# 795494688IHM08M1-DG_V4.net
KiCad netlist of a schematic drawn in Altium Designer
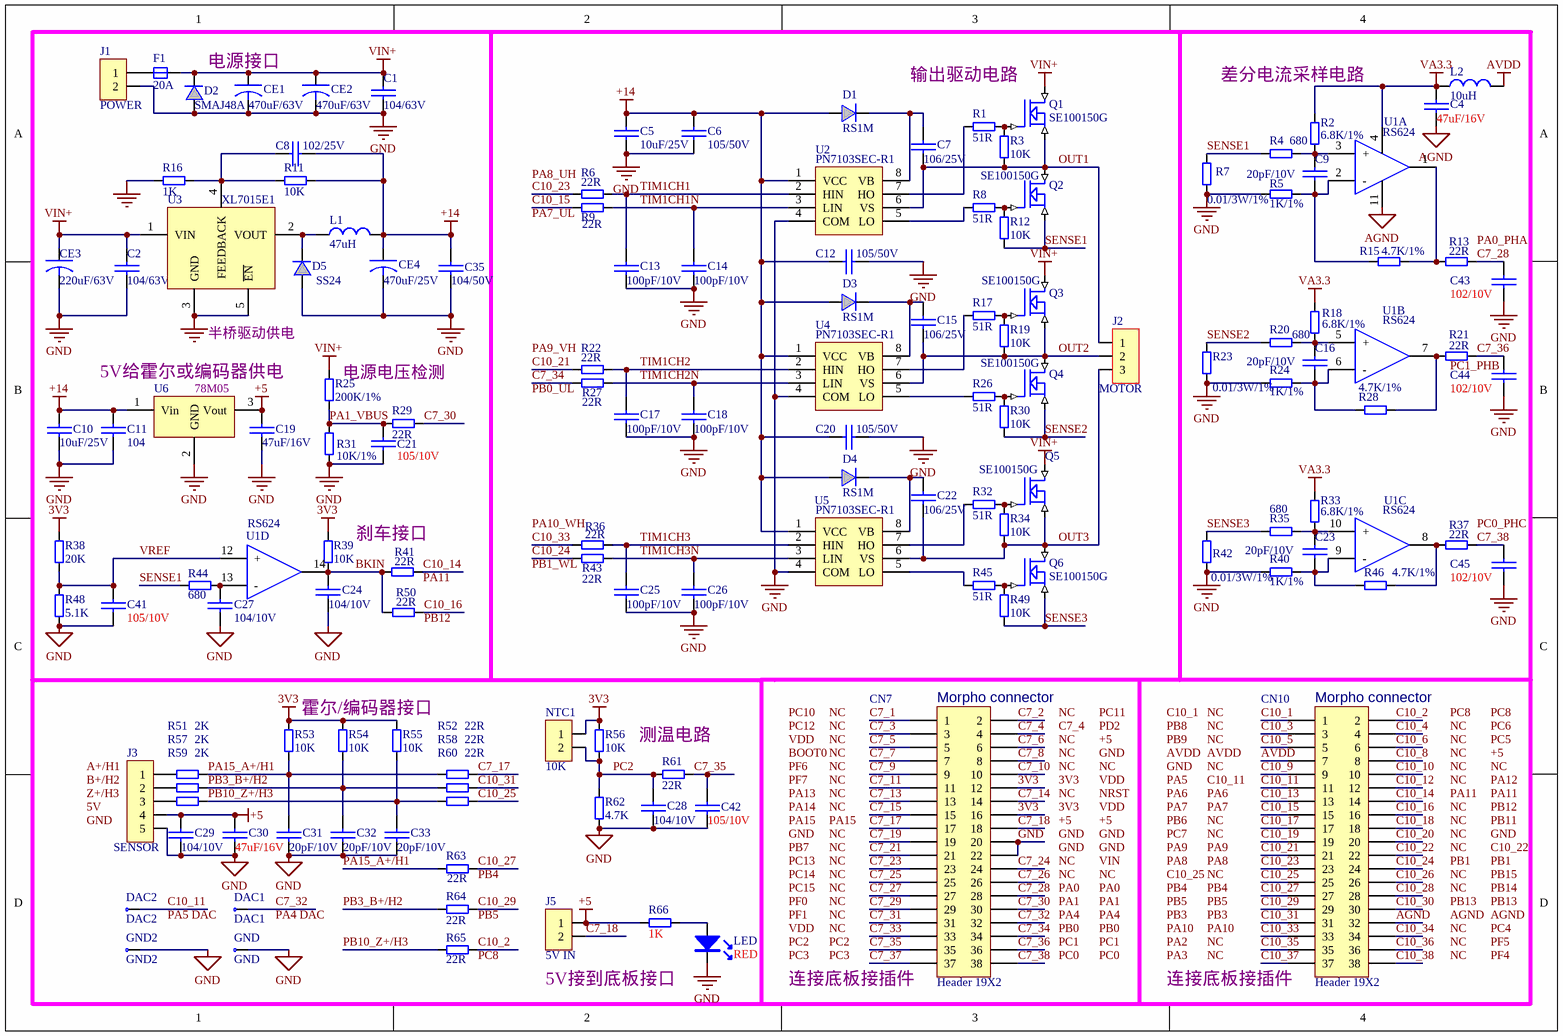
[diagram p0: 795494688IHM08M1-DG_V4.SchDoc]

(export (version "E")
  (design (tool "Eeschema 10.0.6"))
  (components
    (comp (ref "C1")
      (value "104/63V")
      (footprint "0805C")
      (description "C")
      (libsource (lib "zh") (part "C"))
    )
    (comp (ref "C2")
      (value "104/63V")
      (footprint "0805C")
      (description "C")
      (libsource (lib "zh") (part "C"))
    )
    (comp (ref "C4")
      (value "47uF/16V")
      (footprint "0805C")
      (description "C")
      (libsource (lib "zh") (part "C"))
    )
    (comp (ref "C5")
      (value "10uF/25V")
      (footprint "1206C")
      (description "Capacitor")
      (libsource (lib "*") (part "C"))
    )
    (comp (ref "C6")
      (value "105/50V")
      (footprint "0805C")
      (description "C")
      (libsource (lib "zh1") (part "C"))
    )
    (comp (ref "C7")
      (value "106/25V")
      (footprint "1206C")
      (description "C")
      (libsource (lib "zh1") (part "C"))
    )
    (comp (ref "C8")
      (value "102/25V")
      (footprint "0805C")
      (description "Capacitor")
      (libsource (lib "*") (part "C"))
    )
    (comp (ref "C9")
      (value "20pF/10V")
      (footprint "0603C")
      (description "C")
      (libsource (lib "zh") (part "C"))
    )
    (comp (ref "C10")
      (value "10uF/25V")
      (footprint "1206C")
      (description "Capacitor")
      (libsource (lib "*") (part "C"))
    )
    (comp (ref "C11")
      (value "104")
      (footprint "0805C")
      (description "Capacitor")
      (libsource (lib "*") (part "C"))
    )
    (comp (ref "C12")
      (value "105/50V")
      (footprint "0805C")
      (description "C")
      (libsource (lib "zh1") (part "C"))
    )
    (comp (ref "C13")
      (value "100pF/10V")
      (footprint "0603C")
      (description "C")
      (libsource (lib "zh") (part "C"))
    )
    (comp (ref "C14")
      (value "100pF/10V")
      (footprint "0603C")
      (description "C")
      (libsource (lib "zh") (part "C"))
    )
    (comp (ref "C15")
      (value "106/25V")
      (footprint "1206C")
      (description "C")
      (libsource (lib "zh1") (part "C"))
    )
    (comp (ref "C16")
      (value "20pF/10V")
      (footprint "0603C")
      (description "C")
      (libsource (lib "zh") (part "C"))
    )
    (comp (ref "C17")
      (value "100pF/10V")
      (footprint "0603C")
      (description "C")
      (libsource (lib "zh") (part "C"))
    )
    (comp (ref "C18")
      (value "100pF/10V")
      (footprint "0603C")
      (description "C")
      (libsource (lib "zh") (part "C"))
    )
    (comp (ref "C19")
      (value "47uF/16V")
      (footprint "1206C")
      (description "Capacitor")
      (libsource (lib "*") (part "C"))
    )
    (comp (ref "C20")
      (value "105/50V")
      (footprint "0805C")
      (description "C")
      (libsource (lib "zh1") (part "C"))
    )
    (comp (ref "C21")
      (value "105/10V")
      (footprint "0603C")
      (description "C")
      (libsource (lib "zh") (part "C"))
    )
    (comp (ref "C22")
      (value "106/25V")
      (footprint "1206C")
      (description "C")
      (libsource (lib "zh1") (part "C"))
    )
    (comp (ref "C23")
      (value "20pF/10V")
      (footprint "0603C")
      (description "C")
      (libsource (lib "zh") (part "C"))
    )
    (comp (ref "C24")
      (value "104/10V")
      (footprint "0603C")
      (description "C")
      (libsource (lib "zh") (part "C"))
    )
    (comp (ref "C25")
      (value "100pF/10V")
      (footprint "0603C")
      (description "C")
      (libsource (lib "zh") (part "C"))
    )
    (comp (ref "C26")
      (value "100pF/10V")
      (footprint "0603C")
      (description "C")
      (libsource (lib "zh") (part "C"))
    )
    (comp (ref "C27")
      (value "104/10V")
      (footprint "0603C")
      (description "C")
      (libsource (lib "zh") (part "C"))
    )
    (comp (ref "C28")
      (value "104/10V")
      (footprint "0603C")
      (description "C")
      (libsource (lib "zh") (part "C"))
    )
    (comp (ref "C29")
      (value "104/10V")
      (footprint "0603C")
      (description "C")
      (libsource (lib "zh") (part "C"))
    )
    (comp (ref "C30")
      (value "47uF/16V")
      (footprint "0805C")
      (description "C")
      (libsource (lib "zh") (part "C"))
    )
    (comp (ref "C31")
      (value "20pF/10V")
      (footprint "0603C")
      (description "C")
      (libsource (lib "zh") (part "C"))
    )
    (comp (ref "C32")
      (value "20pF/10V")
      (footprint "0603C")
      (description "C")
      (libsource (lib "zh") (part "C"))
    )
    (comp (ref "C33")
      (value "20pF/10V")
      (footprint "0603C")
      (description "C")
      (libsource (lib "zh") (part "C"))
    )
    (comp (ref "C35")
      (value "104/50V")
      (footprint "0805C")
      (description "C")
      (libsource (lib "zh") (part "C"))
    )
    (comp (ref "C41")
      (value "105/10V")
      (footprint "0603C")
      (description "C")
      (libsource (lib "zh") (part "C"))
    )
    (comp (ref "C42")
      (value "105/10V")
      (footprint "0603C")
      (description "C")
      (libsource (lib "zh") (part "C"))
    )
    (comp (ref "C43")
      (value "102/10V")
      (footprint "0603C")
      (description "C")
      (libsource (lib "zh") (part "C"))
    )
    (comp (ref "C44")
      (value "102/10V")
      (footprint "0603C")
      (description "C")
      (libsource (lib "zh") (part "C"))
    )
    (comp (ref "C45")
      (value "102/10V")
      (footprint "0603C")
      (description "C")
      (libsource (lib "zh") (part "C"))
    )
    (comp (ref "CE1")
      (value "470uF/63V")
      (footprint "E5-12.5")
      (description "10uF/25V")
      (libsource (lib "zh") (part "CE"))
    )
    (comp (ref "CE2")
      (value "470uF/63V")
      (footprint "E5-12.5")
      (description "10uF/25V")
      (libsource (lib "zh") (part "CE"))
    )
    (comp (ref "CE3")
      (value "220uF/63V")
      (footprint "E5-10")
      (description "10uF/25V")
      (libsource (lib "zh") (part "CE"))
    )
    (comp (ref "CE4")
      (value "470uF/25V")
      (footprint "E3.5-8.2")
      (description "10uF/25V")
      (libsource (lib "zh") (part "CE"))
    )
    (comp (ref "CN7")
      (value "Header 19X2")
      (footprint "2*19P")
      (description "Header, 19-Pin, Dual row")
      (fields (field (name "PUBLISHER") "Altium Limited"))
      (libsource (lib "Nucleo_64_1") (part "Header 19X2"))
    )
    (comp (ref "CN10")
      (value "Header 19X2")
      (footprint "2*19P")
      (description "Header, 19-Pin, Dual row")
      (fields (field (name "PUBLISHER") "Altium Limited"))
      (libsource (lib "Nucleo_64_1") (part "Header 19X2"))
    )
    (comp (ref "D1") (value "RS1M") (footprint "TP4007") (description "D") (libsource (lib "zh1") (part "D")))
    (comp (ref "D2")
      (value "SMAJ48A")
      (footprint "TPss24")
      (description "D")
      (libsource (lib "zh") (part "D"))
    )
    (comp (ref "D3") (value "RS1M") (footprint "TP4007") (description "D") (libsource (lib "zh1") (part "D")))
    (comp (ref "D4") (value "RS1M") (footprint "TP4007") (description "D") (libsource (lib "zh1") (part "D")))
    (comp (ref "D5") (value "SS24") (footprint "TPss24") (description "D") (libsource (lib "zh") (part "D")))
    (comp (ref "DAC1") (value "DAC1") (footprint "TP-1.5") (libsource (lib "zh") (part "TP")))
    (comp (ref "DAC2") (value "DAC2") (footprint "TP-1.5") (libsource (lib "zh") (part "TP")))
    (comp (ref "F1")
      (value "20A")
      (footprint "F1808")
      (description "FUSE")
      (libsource (lib "zh") (part "FUSE"))
    )
    (comp (ref "GND") (value "GND") (footprint "TP-1.5") (libsource (lib "zh") (part "TP")))
    (comp (ref "GND2") (value "GND2") (footprint "TP-1.5") (libsource (lib "zh") (part "TP")))
    (comp (ref "J1")
      (value "POWER")
      (footprint "POW-5.08-2W")
      (description "J")
      (libsource (lib "zh") (part "CON2"))
    )
    (comp (ref "J2")
      (value "MOTOR")
      (footprint "POW-5.08-3W")
      (description "CN")
      (libsource (lib "zh") (part "CON3"))
    )
    (comp (ref "J3")
      (value "SENSOR")
      (footprint "SIP5")
      (description "CN")
      (libsource (lib "zh") (part "CON5"))
    )
    (comp (ref "J5")
      (value "5V IN")
      (footprint "SIP2")
      (description "J")
      (libsource (lib "zh") (part "CON2"))
    )
    (comp (ref "L1")
      (value "47uH")
      (footprint "L-TB-7*7")
      (description "10uH")
      (libsource (lib "zh1") (part "L"))
    )
    (comp (ref "L2") (value "10uH") (footprint "0603") (libsource (lib "zh1") (part "L")))
    (comp (ref "LED")
      (value "RED")
      (footprint "0603D")
      (description "LED")
      (libsource (lib "zh") (part "LED"))
    )
    (comp (ref "NTC1")
      (value "10K")
      (footprint "SIP2")
      (description "J")
      (libsource (lib "zh") (part "CON2"))
    )
    (comp (ref "Q1") (value "SE100150G") (footprint "TO-263S") (libsource (lib "zh1") (part "MOSFET N")))
    (comp (ref "Q2") (value "SE100150G") (footprint "TO-263S") (libsource (lib "zh1") (part "MOSFET N")))
    (comp (ref "Q3") (value "SE100150G") (footprint "TO-263S") (libsource (lib "zh1") (part "MOSFET N")))
    (comp (ref "Q4") (value "SE100150G") (footprint "TO-263S") (libsource (lib "zh1") (part "MOSFET N")))
    (comp (ref "Q5") (value "SE100150G") (footprint "TO-263S") (libsource (lib "zh1") (part "MOSFET N")))
    (comp (ref "Q6") (value "SE100150G") (footprint "TO-263S") (libsource (lib "zh1") (part "MOSFET N")))
    (comp (ref "R1") (value "51R") (footprint "0805") (description "10K") (libsource (lib "zh1") (part "R")))
    (comp (ref "R2")
      (value "6.8K/1%")
      (footprint "0603")
      (description "10K")
      (libsource (lib "zh") (part "R"))
    )
    (comp (ref "R3") (value "10K") (footprint "0603") (libsource (lib "zh") (part "R")))
    (comp (ref "R4") (value "680") (footprint "0603") (description "10K") (libsource (lib "zh") (part "R")))
    (comp (ref "R5") (value "1K/1%") (footprint "0603") (description "10K") (libsource (lib "zh") (part "R")))
    (comp (ref "R6") (value "22R") (footprint "0603") (description "10K") (libsource (lib "zh") (part "R")))
    (comp (ref "R7")
      (value "0.01/3W/1%")
      (footprint "2512")
      (description "10K")
      (libsource (lib "zh") (part "R"))
    )
    (comp (ref "R8") (value "51R") (footprint "0805") (description "10K") (libsource (lib "zh1") (part "R")))
    (comp (ref "R9") (value "22R") (footprint "0603") (description "10K") (libsource (lib "zh") (part "R")))
    (comp (ref "R11") (value "10K") (footprint "0603") (libsource (lib "zh") (part "R")))
    (comp (ref "R12") (value "10K") (footprint "0603") (libsource (lib "zh") (part "R")))
    (comp (ref "R13") (value "22R") (footprint "0603") (description "10K") (libsource (lib "zh") (part "R")))
    (comp (ref "R15")
      (value "4.7K/1%")
      (footprint "0603")
      (description "10K")
      (libsource (lib "zh") (part "R"))
    )
    (comp (ref "R16") (value "1K") (footprint "0603") (description "10K") (libsource (lib "zh") (part "R")))
    (comp (ref "R17") (value "51R") (footprint "0805") (description "10K") (libsource (lib "zh1") (part "R")))
    (comp (ref "R18")
      (value "6.8K/1%")
      (footprint "0603")
      (description "10K")
      (libsource (lib "zh") (part "R"))
    )
    (comp (ref "R19") (value "10K") (footprint "0603") (libsource (lib "zh") (part "R")))
    (comp (ref "R20") (value "680") (footprint "0603") (description "10K") (libsource (lib "zh") (part "R")))
    (comp (ref "R21") (value "22R") (footprint "0603") (description "10K") (libsource (lib "zh") (part "R")))
    (comp (ref "R22") (value "22R") (footprint "0603") (description "10K") (libsource (lib "zh") (part "R")))
    (comp (ref "R23")
      (value "0.01/3W/1%")
      (footprint "2512")
      (description "10K")
      (libsource (lib "zh") (part "R"))
    )
    (comp (ref "R24")
      (value "1K/1%")
      (footprint "0603")
      (description "10K")
      (libsource (lib "zh") (part "R"))
    )
    (comp (ref "R25")
      (value "200K/1%")
      (footprint "0603")
      (description "10K")
      (libsource (lib "zh") (part "R"))
    )
    (comp (ref "R26") (value "51R") (footprint "0805") (description "10K") (libsource (lib "zh1") (part "R")))
    (comp (ref "R27") (value "22R") (footprint "0603") (description "10K") (libsource (lib "zh") (part "R")))
    (comp (ref "R28")
      (value "4.7K/1%")
      (footprint "0603")
      (description "10K")
      (libsource (lib "zh") (part "R"))
    )
    (comp (ref "R29") (value "22R") (footprint "0603") (description "10K") (libsource (lib "zh") (part "R")))
    (comp (ref "R30") (value "10K") (footprint "0603") (libsource (lib "zh") (part "R")))
    (comp (ref "R31")
      (value "10K/1%")
      (footprint "0603")
      (description "10K")
      (libsource (lib "zh") (part "R"))
    )
    (comp (ref "R32") (value "51R") (footprint "0805") (description "10K") (libsource (lib "zh1") (part "R")))
    (comp (ref "R33")
      (value "6.8K/1%")
      (footprint "0603")
      (description "10K")
      (libsource (lib "zh") (part "R"))
    )
    (comp (ref "R34") (value "10K") (footprint "0603") (libsource (lib "zh") (part "R")))
    (comp (ref "R35") (value "680") (footprint "0603") (description "10K") (libsource (lib "zh") (part "R")))
    (comp (ref "R36") (value "22R") (footprint "0603") (description "10K") (libsource (lib "zh") (part "R")))
    (comp (ref "R37") (value "22R") (footprint "0603") (description "10K") (libsource (lib "zh") (part "R")))
    (comp (ref "R38") (value "20K") (footprint "0603") (description "10K") (libsource (lib "zh") (part "R")))
    (comp (ref "R39") (value "10K") (footprint "0603") (libsource (lib "zh") (part "R")))
    (comp (ref "R40")
      (value "1K/1%")
      (footprint "0603")
      (description "10K")
      (libsource (lib "zh") (part "R"))
    )
    (comp (ref "R41") (value "22R") (footprint "0603") (description "10K") (libsource (lib "zh") (part "R")))
    (comp (ref "R42")
      (value "0.01/3W/1%")
      (footprint "2512")
      (description "10K")
      (libsource (lib "zh") (part "R"))
    )
    (comp (ref "R43") (value "22R") (footprint "0603") (description "10K") (libsource (lib "zh") (part "R")))
    (comp (ref "R44") (value "680") (footprint "0603") (description "10K") (libsource (lib "zh") (part "R")))
    (comp (ref "R45") (value "51R") (footprint "0805") (description "10K") (libsource (lib "zh1") (part "R")))
    (comp (ref "R46")
      (value "4.7K/1%")
      (footprint "0603")
      (description "10K")
      (libsource (lib "zh") (part "R"))
    )
    (comp (ref "R48") (value "5.1K") (footprint "0603") (description "10K") (libsource (lib "zh") (part "R")))
    (comp (ref "R49") (value "10K") (footprint "0603") (libsource (lib "zh") (part "R")))
    (comp (ref "R50") (value "22R") (footprint "0603") (description "10K") (libsource (lib "zh") (part "R")))
    (comp (ref "R51") (value "2K") (footprint "0603") (description "10K") (libsource (lib "zh") (part "R")))
    (comp (ref "R52") (value "22R") (footprint "0603") (description "10K") (libsource (lib "zh") (part "R")))
    (comp (ref "R53") (value "10K") (footprint "0603") (libsource (lib "zh") (part "R")))
    (comp (ref "R54") (value "10K") (footprint "0603") (libsource (lib "zh") (part "R")))
    (comp (ref "R55") (value "10K") (footprint "0603") (libsource (lib "zh") (part "R")))
    (comp (ref "R56") (value "10K") (footprint "0805") (libsource (lib "zh") (part "R")))
    (comp (ref "R57") (value "2K") (footprint "0603") (description "10K") (libsource (lib "zh") (part "R")))
    (comp (ref "R58") (value "22R") (footprint "0603") (description "10K") (libsource (lib "zh") (part "R")))
    (comp (ref "R59") (value "2K") (footprint "0603") (description "10K") (libsource (lib "zh") (part "R")))
    (comp (ref "R60") (value "22R") (footprint "0603") (description "10K") (libsource (lib "zh") (part "R")))
    (comp (ref "R61") (value "22R") (footprint "0603") (description "10K") (libsource (lib "zh") (part "R")))
    (comp (ref "R62") (value "4.7K") (footprint "0603") (description "10K") (libsource (lib "zh") (part "R")))
    (comp (ref "R63") (value "22R") (footprint "0603") (description "10K") (libsource (lib "zh") (part "R")))
    (comp (ref "R64") (value "22R") (footprint "0603") (description "10K") (libsource (lib "zh") (part "R")))
    (comp (ref "R65") (value "22R") (footprint "0603") (description "10K") (libsource (lib "zh") (part "R")))
    (comp (ref "R66") (value "1K") (footprint "0603") (description "10K") (libsource (lib "zh") (part "R")))
    (comp (ref "U1") (value "RS624") (footprint "SO-14") (libsource (lib "LY-SCH") (part "LM324")))
    (comp (ref "U2") (value "PN7103SEC-R1") (footprint "SO-8") (libsource (lib "zh1") (part "IR2101S")))
    (comp (ref "U3")
      (value "XL7015E1")
      (footprint "TO-252-5L")
      (libsource (lib "LY-SCH") (part "XL1507-ADJ"))
    )
    (comp (ref "U4") (value "PN7103SEC-R1") (footprint "SO-8") (libsource (lib "zh1") (part "IR2101S")))
    (comp (ref "U5") (value "PN7103SEC-R1") (footprint "SO-8") (libsource (lib "zh1") (part "IR2101S")))
    (comp (ref "U6")
      (value "78M05")
      (footprint "TO-252AA")
      (description "IC")
      (libsource (lib "zh1") (part "7805S"))
    )
  )
  (nets
    (net (code "1") (name "+5") (class "Default")
      (node (ref "C19") (pin "2") (pintype "passive"))
      (node (ref "C29") (pin "1") (pintype "passive"))
      (node (ref "C30") (pin "1") (pintype "passive"))
      (node (ref "J3") (pin "4") (pinfunction "4_4") (pintype "passive"))
      (node (ref "J5") (pin "1") (pinfunction "1_1") (pintype "passive"))
      (node (ref "R66") (pin "2") (pinfunction "2_2") (pintype "passive"))
      (node (ref "U6") (pin "3") (pinfunction "Vout_3") (pintype "passive"))
    )
    (net (code "2") (name "+14") (class "Default")
      (node (ref "C10") (pin "2") (pintype "passive"))
      (node (ref "C11") (pin "2") (pintype "passive"))
      (node (ref "C12") (pin "1") (pintype "passive"))
      (node (ref "C20") (pin "1") (pintype "passive"))
      (node (ref "C35") (pin "1") (pintype "passive"))
      (node (ref "C5") (pin "2") (pintype "passive"))
      (node (ref "C6") (pin "1") (pintype "passive"))
      (node (ref "C8") (pin "1") (pintype "passive"))
      (node (ref "CE4") (pin "1") (pinfunction "1_1") (pintype "passive"))
      (node (ref "D1") (pin "A") (pinfunction "1_A") (pintype "passive"))
      (node (ref "D3") (pin "A") (pinfunction "1_A") (pintype "passive"))
      (node (ref "D4") (pin "A") (pinfunction "1_A") (pintype "passive"))
      (node (ref "L1") (pin "2") (pinfunction "2_2") (pintype "passive"))
      (node (ref "R11") (pin "2") (pinfunction "2_2") (pintype "passive"))
      (node (ref "U2") (pin "1") (pinfunction "VCC_1") (pintype "passive"))
      (node (ref "U4") (pin "1") (pinfunction "VCC_1") (pintype "passive"))
      (node (ref "U5") (pin "1") (pinfunction "VCC_1") (pintype "passive"))
      (node (ref "U6") (pin "1") (pinfunction "Vin_1") (pintype "passive"))
    )
    (net (code "6") (name "/BKIN") (class "Default")
      (node (ref "C24") (pin "1") (pintype "passive"))
      (node (ref "R39") (pin "1") (pinfunction "1_1") (pintype "passive"))
      (node (ref "R41") (pin "1") (pinfunction "1_1") (pintype "passive"))
      (node (ref "R50") (pin "1") (pinfunction "1_1") (pintype "passive"))
      (node (ref "U1") (pin "14") (pinfunction "O_14") (pintype "passive"))
    )
    (net (code "8") (name "/C7_1") (class "Default")
      (node (ref "CN7") (pin "1") (pinfunction "1_1") (pintype "passive"))
    )
    (net (code "9") (name "/C7_2") (class "Default")
      (node (ref "CN7") (pin "2") (pinfunction "2_2") (pintype "passive"))
    )
    (net (code "10") (name "/C7_3") (class "Default")
      (node (ref "CN7") (pin "3") (pinfunction "3_3") (pintype "passive"))
    )
    (net (code "11") (name "/C7_4") (class "Default")
      (node (ref "CN7") (pin "4") (pinfunction "4_4") (pintype "passive"))
    )
    (net (code "12") (name "/C7_5") (class "Default")
      (node (ref "CN7") (pin "5") (pinfunction "5_5") (pintype "passive"))
    )
    (net (code "13") (name "/C7_6") (class "Default")
      (node (ref "CN7") (pin "6") (pinfunction "6_6") (pintype "passive"))
    )
    (net (code "14") (name "/C7_7") (class "Default")
      (node (ref "CN7") (pin "7") (pinfunction "7_7") (pintype "passive"))
    )
    (net (code "15") (name "/C7_8") (class "Default")
      (node (ref "CN7") (pin "8") (pinfunction "8_8") (pintype "passive"))
    )
    (net (code "16") (name "/C7_9") (class "Default")
      (node (ref "CN7") (pin "9") (pinfunction "9_9") (pintype "passive"))
    )
    (net (code "17") (name "/C7_10") (class "Default")
      (node (ref "CN7") (pin "10") (pinfunction "10_10") (pintype "passive"))
    )
    (net (code "18") (name "/C7_11") (class "Default")
      (node (ref "CN7") (pin "11") (pinfunction "11_11") (pintype "passive"))
    )
    (net (code "19") (name "/C7_13") (class "Default")
      (node (ref "CN7") (pin "13") (pinfunction "13_13") (pintype "passive"))
    )
    (net (code "20") (name "/C7_14") (class "Default")
      (node (ref "CN7") (pin "14") (pinfunction "14_14") (pintype "passive"))
    )
    (net (code "21") (name "/C7_15") (class "Default")
      (node (ref "CN7") (pin "15") (pinfunction "15_15") (pintype "passive"))
    )
    (net (code "22") (name "/C7_17") (class "Default")
      (node (ref "CN7") (pin "17") (pinfunction "17_17") (pintype "passive"))
      (node (ref "R52") (pin "1") (pinfunction "1_1") (pintype "passive"))
    )
    (net (code "23") (name "/C7_18") (class "Default")
      (node (ref "CN7") (pin "18") (pinfunction "18_18") (pintype "passive"))
      (node (ref "J5") (pin "2") (pinfunction "2_2") (pintype "passive"))
    )
    (net (code "24") (name "/C7_19") (class "Default")
      (node (ref "CN7") (pin "19") (pinfunction "19_19") (pintype "passive"))
    )
    (net (code "25") (name "/C7_21") (class "Default")
      (node (ref "CN7") (pin "21") (pinfunction "21_21") (pintype "passive"))
    )
    (net (code "26") (name "/C7_23") (class "Default")
      (node (ref "CN7") (pin "23") (pinfunction "23_23") (pintype "passive"))
    )
    (net (code "27") (name "/C7_24") (class "Default")
      (node (ref "CN7") (pin "24") (pinfunction "24_24") (pintype "passive"))
    )
    (net (code "28") (name "/C7_25") (class "Default")
      (node (ref "CN7") (pin "25") (pinfunction "25_25") (pintype "passive"))
    )
    (net (code "29") (name "/C7_26") (class "Default")
      (node (ref "CN7") (pin "26") (pinfunction "26_26") (pintype "passive"))
    )
    (net (code "30") (name "/C7_27") (class "Default")
      (node (ref "CN7") (pin "27") (pinfunction "27_27") (pintype "passive"))
    )
    (net (code "31") (name "/C7_28") (class "Default")
      (node (ref "C43") (pin "1") (pintype "passive"))
      (node (ref "CN7") (pin "28") (pinfunction "28_28") (pintype "passive"))
      (node (ref "R13") (pin "2") (pinfunction "2_2") (pintype "passive"))
    )
    (net (code "32") (name "/C7_29") (class "Default")
      (node (ref "CN7") (pin "29") (pinfunction "29_29") (pintype "passive"))
    )
    (net (code "33") (name "/C7_30") (class "Default")
      (node (ref "CN7") (pin "30") (pinfunction "30_30") (pintype "passive"))
      (node (ref "R29") (pin "2") (pinfunction "2_2") (pintype "passive"))
    )
    (net (code "34") (name "/C7_31") (class "Default")
      (node (ref "CN7") (pin "31") (pinfunction "31_31") (pintype "passive"))
    )
    (net (code "35") (name "/C7_32") (class "Default")
      (node (ref "CN7") (pin "32") (pinfunction "32_32") (pintype "passive"))
      (node (ref "DAC1") (pin "1") (pinfunction "1_1") (pintype "passive"))
    )
    (net (code "36") (name "/C7_33") (class "Default")
      (node (ref "CN7") (pin "33") (pinfunction "33_33") (pintype "passive"))
    )
    (net (code "37") (name "/C7_34") (class "Default")
      (node (ref "CN7") (pin "34") (pinfunction "34_34") (pintype "passive"))
      (node (ref "R27") (pin "1") (pinfunction "1_1") (pintype "passive"))
    )
    (net (code "38") (name "/C7_35") (class "Default")
      (node (ref "C42") (pin "1") (pintype "passive"))
      (node (ref "CN7") (pin "35") (pinfunction "35_35") (pintype "passive"))
      (node (ref "R61") (pin "1") (pinfunction "1_1") (pintype "passive"))
    )
    (net (code "39") (name "/C7_36") (class "Default")
      (node (ref "C44") (pin "1") (pintype "passive"))
      (node (ref "CN7") (pin "36") (pinfunction "36_36") (pintype "passive"))
      (node (ref "R21") (pin "2") (pinfunction "2_2") (pintype "passive"))
    )
    (net (code "40") (name "/C7_37") (class "Default")
      (node (ref "CN7") (pin "37") (pinfunction "37_37") (pintype "passive"))
    )
    (net (code "41") (name "/C7_38") (class "Default")
      (node (ref "C45") (pin "1") (pintype "passive"))
      (node (ref "CN7") (pin "38") (pinfunction "38_38") (pintype "passive"))
      (node (ref "R37") (pin "2") (pinfunction "2_2") (pintype "passive"))
    )
    (net (code "42") (name "/C10_1") (class "Default")
      (node (ref "CN10") (pin "1") (pinfunction "1_1") (pintype "passive"))
    )
    (net (code "43") (name "/C10_2") (class "Default")
      (node (ref "CN10") (pin "2") (pinfunction "2_2") (pintype "passive"))
      (node (ref "R65") (pin "1") (pinfunction "1_1") (pintype "passive"))
    )
    (net (code "44") (name "/C10_3") (class "Default")
      (node (ref "CN10") (pin "3") (pinfunction "3_3") (pintype "passive"))
    )
    (net (code "45") (name "/C10_4") (class "Default")
      (node (ref "CN10") (pin "4") (pinfunction "4_4") (pintype "passive"))
    )
    (net (code "46") (name "/C10_5") (class "Default")
      (node (ref "CN10") (pin "5") (pinfunction "5_5") (pintype "passive"))
    )
    (net (code "47") (name "/C10_6") (class "Default")
      (node (ref "CN10") (pin "6") (pinfunction "6_6") (pintype "passive"))
    )
    (net (code "48") (name "/C10_8") (class "Default")
      (node (ref "CN10") (pin "8") (pinfunction "8_8") (pintype "passive"))
    )
    (net (code "49") (name "/C10_9") (class "Default")
      (node (ref "CN10") (pin "9") (pinfunction "9_9") (pintype "passive"))
    )
    (net (code "50") (name "/C10_10") (class "Default")
      (node (ref "CN10") (pin "10") (pinfunction "10_10") (pintype "passive"))
    )
    (net (code "51") (name "/C10_11") (class "Default")
      (node (ref "CN10") (pin "11") (pinfunction "11_11") (pintype "passive"))
      (node (ref "DAC2") (pin "1") (pinfunction "1_1") (pintype "passive"))
    )
    (net (code "52") (name "/C10_12") (class "Default")
      (node (ref "CN10") (pin "12") (pinfunction "12_12") (pintype "passive"))
    )
    (net (code "53") (name "/C10_13") (class "Default")
      (node (ref "CN10") (pin "13") (pinfunction "13_13") (pintype "passive"))
    )
    (net (code "54") (name "/C10_14") (class "Default")
      (node (ref "CN10") (pin "14") (pinfunction "14_14") (pintype "passive"))
      (node (ref "R41") (pin "2") (pinfunction "2_2") (pintype "passive"))
    )
    (net (code "55") (name "/C10_15") (class "Default")
      (node (ref "CN10") (pin "15") (pinfunction "15_15") (pintype "passive"))
      (node (ref "R9") (pin "1") (pinfunction "1_1") (pintype "passive"))
    )
    (net (code "56") (name "/C10_16") (class "Default")
      (node (ref "CN10") (pin "16") (pinfunction "16_16") (pintype "passive"))
      (node (ref "R50") (pin "2") (pinfunction "2_2") (pintype "passive"))
    )
    (net (code "57") (name "/C10_17") (class "Default")
      (node (ref "CN10") (pin "17") (pinfunction "17_17") (pintype "passive"))
    )
    (net (code "58") (name "/C10_18") (class "Default")
      (node (ref "CN10") (pin "18") (pinfunction "18_18") (pintype "passive"))
    )
    (net (code "59") (name "/C10_19") (class "Default")
      (node (ref "CN10") (pin "19") (pinfunction "19_19") (pintype "passive"))
    )
    (net (code "60") (name "/C10_20") (class "Default")
      (node (ref "CN10") (pin "20") (pinfunction "20_20") (pintype "passive"))
    )
    (net (code "61") (name "/C10_21") (class "Default")
      (node (ref "CN10") (pin "21") (pinfunction "21_21") (pintype "passive"))
      (node (ref "R22") (pin "1") (pinfunction "1_1") (pintype "passive"))
    )
    (net (code "62") (name "/C10_22") (class "Default")
      (node (ref "CN10") (pin "22") (pinfunction "22_22") (pintype "passive"))
    )
    (net (code "63") (name "/C10_23") (class "Default")
      (node (ref "CN10") (pin "23") (pinfunction "23_23") (pintype "passive"))
      (node (ref "R6") (pin "1") (pinfunction "1_1") (pintype "passive"))
    )
    (net (code "64") (name "/C10_24") (class "Default")
      (node (ref "CN10") (pin "24") (pinfunction "24_24") (pintype "passive"))
      (node (ref "R43") (pin "1") (pinfunction "1_1") (pintype "passive"))
    )
    (net (code "65") (name "/C10_25") (class "Default")
      (node (ref "CN10") (pin "25") (pinfunction "25_25") (pintype "passive"))
      (node (ref "R60") (pin "1") (pinfunction "1_1") (pintype "passive"))
    )
    (net (code "66") (name "/C10_26") (class "Default")
      (node (ref "CN10") (pin "26") (pinfunction "26_26") (pintype "passive"))
    )
    (net (code "67") (name "/C10_27") (class "Default")
      (node (ref "CN10") (pin "27") (pinfunction "27_27") (pintype "passive"))
      (node (ref "R63") (pin "1") (pinfunction "1_1") (pintype "passive"))
    )
    (net (code "68") (name "/C10_28") (class "Default")
      (node (ref "CN10") (pin "28") (pinfunction "28_28") (pintype "passive"))
    )
    (net (code "69") (name "/C10_29") (class "Default")
      (node (ref "CN10") (pin "29") (pinfunction "29_29") (pintype "passive"))
      (node (ref "R64") (pin "1") (pinfunction "1_1") (pintype "passive"))
    )
    (net (code "70") (name "/C10_30") (class "Default")
      (node (ref "CN10") (pin "30") (pinfunction "30_30") (pintype "passive"))
    )
    (net (code "71") (name "/C10_31") (class "Default")
      (node (ref "CN10") (pin "31") (pinfunction "31_31") (pintype "passive"))
      (node (ref "R58") (pin "1") (pinfunction "1_1") (pintype "passive"))
    )
    (net (code "72") (name "/C10_33") (class "Default")
      (node (ref "CN10") (pin "33") (pinfunction "33_33") (pintype "passive"))
      (node (ref "R36") (pin "1") (pinfunction "1_1") (pintype "passive"))
    )
    (net (code "73") (name "/C10_34") (class "Default")
      (node (ref "CN10") (pin "34") (pinfunction "34_34") (pintype "passive"))
    )
    (net (code "74") (name "/C10_35") (class "Default")
      (node (ref "CN10") (pin "35") (pinfunction "35_35") (pintype "passive"))
    )
    (net (code "75") (name "/C10_36") (class "Default")
      (node (ref "CN10") (pin "36") (pinfunction "36_36") (pintype "passive"))
    )
    (net (code "76") (name "/C10_37") (class "Default")
      (node (ref "CN10") (pin "37") (pinfunction "37_37") (pintype "passive"))
    )
    (net (code "77") (name "/C10_38") (class "Default")
      (node (ref "CN10") (pin "38") (pinfunction "38_38") (pintype "passive"))
    )
    (net (code "80") (name "/OUT1") (class "Default")
      (node (ref "C7") (pin "2") (pintype "passive"))
      (node (ref "J2") (pin "1") (pinfunction "1_1") (pintype "passive"))
      (node (ref "Q1") (pin "3") (pinfunction "S_3") (pintype "input"))
      (node (ref "Q2") (pin "2") (pinfunction "D_2") (pintype "input"))
      (node (ref "R3") (pin "1") (pinfunction "1_1") (pintype "passive"))
      (node (ref "U2") (pin "6") (pinfunction "VS_6") (pintype "passive"))
    )
    (net (code "81") (name "/OUT2") (class "Default")
      (node (ref "C15") (pin "2") (pintype "passive"))
      (node (ref "J2") (pin "2") (pinfunction "2_2") (pintype "passive"))
      (node (ref "Q3") (pin "3") (pinfunction "S_3") (pintype "input"))
      (node (ref "Q4") (pin "2") (pinfunction "D_2") (pintype "input"))
      (node (ref "R19") (pin "1") (pinfunction "1_1") (pintype "passive"))
      (node (ref "U4") (pin "6") (pinfunction "VS_6") (pintype "passive"))
    )
    (net (code "82") (name "/OUT3") (class "Default")
      (node (ref "C22") (pin "2") (pintype "passive"))
      (node (ref "J2") (pin "3") (pinfunction "3_3") (pintype "passive"))
      (node (ref "Q5") (pin "3") (pinfunction "S_3") (pintype "input"))
      (node (ref "Q6") (pin "2") (pinfunction "D_2") (pintype "input"))
      (node (ref "R34") (pin "1") (pinfunction "1_1") (pintype "passive"))
      (node (ref "U5") (pin "6") (pinfunction "VS_6") (pintype "passive"))
    )
    (net (code "86") (name "/PA1_VBUS") (class "Default")
      (node (ref "C21") (pin "1") (pintype "passive"))
      (node (ref "R25") (pin "1") (pinfunction "1_1") (pintype "passive"))
      (node (ref "R29") (pin "1") (pinfunction "1_1") (pintype "passive"))
      (node (ref "R31") (pin "2") (pinfunction "2_2") (pintype "passive"))
    )
    (net (code "107") (name "/PA15_A+{slash}H1") (class "Default")
      (node (ref "C31") (pin "1") (pintype "passive"))
      (node (ref "R51") (pin "2") (pinfunction "2_2") (pintype "passive"))
      (node (ref "R52") (pin "2") (pinfunction "2_2") (pintype "passive"))
      (node (ref "R53") (pin "1") (pinfunction "1_1") (pintype "passive"))
      (node (ref "R63") (pin "2") (pinfunction "2_2") (pintype "passive"))
    )
    (net (code "113") (name "/PB3_B+{slash}H2") (class "Default")
      (node (ref "C32") (pin "1") (pintype "passive"))
      (node (ref "R54") (pin "1") (pinfunction "1_1") (pintype "passive"))
      (node (ref "R57") (pin "2") (pinfunction "2_2") (pintype "passive"))
      (node (ref "R58") (pin "2") (pinfunction "2_2") (pintype "passive"))
      (node (ref "R64") (pin "2") (pinfunction "2_2") (pintype "passive"))
    )
    (net (code "120") (name "/PB10_Z+{slash}H3") (class "Default")
      (node (ref "C33") (pin "1") (pintype "passive"))
      (node (ref "R55") (pin "1") (pinfunction "1_1") (pintype "passive"))
      (node (ref "R59") (pin "2") (pinfunction "2_2") (pintype "passive"))
      (node (ref "R60") (pin "2") (pinfunction "2_2") (pintype "passive"))
      (node (ref "R65") (pin "2") (pinfunction "2_2") (pintype "passive"))
    )
    (net (code "130") (name "/PC2") (class "Default")
      (node (ref "C28") (pin "1") (pintype "passive"))
      (node (ref "NTC1") (pin "2") (pinfunction "2_2") (pintype "passive"))
      (node (ref "R56") (pin "1") (pinfunction "1_1") (pintype "passive"))
      (node (ref "R61") (pin "2") (pinfunction "2_2") (pintype "passive"))
      (node (ref "R62") (pin "2") (pinfunction "2_2") (pintype "passive"))
    )
    (net (code "150") (name "/SENSE1") (class "Default")
      (node (ref "Q2") (pin "3") (pinfunction "S_3") (pintype "input"))
      (node (ref "R12") (pin "1") (pinfunction "1_1") (pintype "passive"))
      (node (ref "R4") (pin "1") (pinfunction "1_1") (pintype "passive"))
      (node (ref "R44") (pin "1") (pinfunction "1_1") (pintype "passive"))
      (node (ref "R7") (pin "2") (pinfunction "2_2") (pintype "passive"))
    )
    (net (code "151") (name "/SENSE2") (class "Default")
      (node (ref "Q4") (pin "3") (pinfunction "S_3") (pintype "input"))
      (node (ref "R20") (pin "1") (pinfunction "1_1") (pintype "passive"))
      (node (ref "R23") (pin "2") (pinfunction "2_2") (pintype "passive"))
      (node (ref "R30") (pin "1") (pinfunction "1_1") (pintype "passive"))
    )
    (net (code "152") (name "/SENSE3") (class "Default")
      (node (ref "Q6") (pin "3") (pinfunction "S_3") (pintype "input"))
      (node (ref "R35") (pin "1") (pinfunction "1_1") (pintype "passive"))
      (node (ref "R42") (pin "2") (pinfunction "2_2") (pintype "passive"))
      (node (ref "R49") (pin "1") (pinfunction "1_1") (pintype "passive"))
    )
    (net (code "153") (name "/TIM1CH1") (class "Default")
      (node (ref "C13") (pin "1") (pintype "passive"))
      (node (ref "R6") (pin "2") (pinfunction "2_2") (pintype "passive"))
      (node (ref "U2") (pin "2") (pinfunction "HIN_2") (pintype "passive"))
    )
    (net (code "154") (name "/TIM1CH1N") (class "Default")
      (node (ref "C14") (pin "1") (pintype "passive"))
      (node (ref "R9") (pin "2") (pinfunction "2_2") (pintype "passive"))
      (node (ref "U2") (pin "3") (pinfunction "LIN_3") (pintype "passive"))
    )
    (net (code "155") (name "/TIM1CH2") (class "Default")
      (node (ref "C17") (pin "1") (pintype "passive"))
      (node (ref "R22") (pin "2") (pinfunction "2_2") (pintype "passive"))
      (node (ref "U4") (pin "2") (pinfunction "HIN_2") (pintype "passive"))
    )
    (net (code "156") (name "/TIM1CH2N") (class "Default")
      (node (ref "C18") (pin "1") (pintype "passive"))
      (node (ref "R27") (pin "2") (pinfunction "2_2") (pintype "passive"))
      (node (ref "U4") (pin "3") (pinfunction "LIN_3") (pintype "passive"))
    )
    (net (code "157") (name "/TIM1CH3") (class "Default")
      (node (ref "C25") (pin "1") (pintype "passive"))
      (node (ref "R36") (pin "2") (pinfunction "2_2") (pintype "passive"))
      (node (ref "U5") (pin "2") (pinfunction "HIN_2") (pintype "passive"))
    )
    (net (code "158") (name "/TIM1CH3N") (class "Default")
      (node (ref "C26") (pin "1") (pintype "passive"))
      (node (ref "R43") (pin "2") (pinfunction "2_2") (pintype "passive"))
      (node (ref "U5") (pin "3") (pinfunction "LIN_3") (pintype "passive"))
    )
    (net (code "161") (name "/VREF") (class "Default")
      (node (ref "C41") (pin "1") (pintype "passive"))
      (node (ref "R38") (pin "1") (pinfunction "1_1") (pintype "passive"))
      (node (ref "R48") (pin "2") (pinfunction "2_2") (pintype "passive"))
      (node (ref "U1") (pin "12") (pinfunction "+_12") (pintype "passive"))
    )
    (net (code "163") (name "3V3") (class "Default")
      (node (ref "CN7") (pin "12") (pinfunction "12_12") (pintype "passive"))
      (node (ref "CN7") (pin "16") (pinfunction "16_16") (pintype "passive"))
      (node (ref "NTC1") (pin "1") (pinfunction "1_1") (pintype "passive"))
      (node (ref "R38") (pin "2") (pinfunction "2_2") (pintype "passive"))
      (node (ref "R39") (pin "2") (pinfunction "2_2") (pintype "passive"))
      (node (ref "R53") (pin "2") (pinfunction "2_2") (pintype "passive"))
      (node (ref "R54") (pin "2") (pinfunction "2_2") (pintype "passive"))
      (node (ref "R55") (pin "2") (pinfunction "2_2") (pintype "passive"))
      (node (ref "R56") (pin "2") (pinfunction "2_2") (pintype "passive"))
    )
    (net (code "164") (name "AGND") (class "Default")
      (node (ref "C4") (pin "2") (pintype "passive"))
      (node (ref "CN10") (pin "32") (pinfunction "32_32") (pintype "passive"))
      (node (ref "U1") (pin "11") (pinfunction "V-_11") (pintype "passive"))
    )
    (net (code "165") (name "AVDD") (class "Default")
      (node (ref "CN10") (pin "7") (pinfunction "7_7") (pintype "passive"))
      (node (ref "L2") (pin "2") (pinfunction "2_2") (pintype "passive"))
    )
    (net (code "166") (name "GND") (class "Default")
      (node (ref "C1") (pin "2") (pintype "passive"))
      (node (ref "C10") (pin "1") (pintype "passive"))
      (node (ref "C11") (pin "1") (pintype "passive"))
      (node (ref "C12") (pin "2") (pintype "passive"))
      (node (ref "C13") (pin "2") (pintype "passive"))
      (node (ref "C14") (pin "2") (pintype "passive"))
      (node (ref "C17") (pin "2") (pintype "passive"))
      (node (ref "C18") (pin "2") (pintype "passive"))
      (node (ref "C19") (pin "1") (pintype "passive"))
      (node (ref "C2") (pin "2") (pintype "passive"))
      (node (ref "C20") (pin "2") (pintype "passive"))
      (node (ref "C21") (pin "2") (pintype "passive"))
      (node (ref "C24") (pin "2") (pintype "passive"))
      (node (ref "C25") (pin "2") (pintype "passive"))
      (node (ref "C26") (pin "2") (pintype "passive"))
      (node (ref "C27") (pin "2") (pintype "passive"))
      (node (ref "C28") (pin "2") (pintype "passive"))
      (node (ref "C29") (pin "2") (pintype "passive"))
      (node (ref "C30") (pin "2") (pintype "passive"))
      (node (ref "C31") (pin "2") (pintype "passive"))
      (node (ref "C32") (pin "2") (pintype "passive"))
      (node (ref "C33") (pin "2") (pintype "passive"))
      (node (ref "C35") (pin "2") (pintype "passive"))
      (node (ref "C41") (pin "2") (pintype "passive"))
      (node (ref "C42") (pin "2") (pintype "passive"))
      (node (ref "C43") (pin "2") (pintype "passive"))
      (node (ref "C44") (pin "2") (pintype "passive"))
      (node (ref "C45") (pin "2") (pintype "passive"))
      (node (ref "C5") (pin "1") (pintype "passive"))
      (node (ref "C6") (pin "2") (pintype "passive"))
      (node (ref "CE1") (pin "2") (pinfunction "2_2") (pintype "passive"))
      (node (ref "CE2") (pin "2") (pinfunction "2_2") (pintype "passive"))
      (node (ref "CE3") (pin "2") (pinfunction "2_2") (pintype "passive"))
      (node (ref "CE4") (pin "2") (pinfunction "2_2") (pintype "passive"))
      (node (ref "CN7") (pin "20") (pinfunction "20_20") (pintype "passive"))
      (node (ref "CN7") (pin "22") (pinfunction "22_22") (pintype "passive"))
      (node (ref "D2") (pin "A") (pinfunction "1_A") (pintype "passive"))
      (node (ref "D5") (pin "A") (pinfunction "1_A") (pintype "passive"))
      (node (ref "GND") (pin "1") (pinfunction "1_1") (pintype "passive"))
      (node (ref "GND2") (pin "1") (pinfunction "1_1") (pintype "passive"))
      (node (ref "J1") (pin "2") (pinfunction "2_2") (pintype "passive"))
      (node (ref "J3") (pin "5") (pinfunction "5_5") (pintype "passive"))
      (node (ref "LED") (pin "K") (pinfunction "K_K") (pintype "passive"))
      (node (ref "R16") (pin "1") (pinfunction "1_1") (pintype "passive"))
      (node (ref "R23") (pin "1") (pinfunction "1_1") (pintype "passive"))
      (node (ref "R24") (pin "1") (pinfunction "1_1") (pintype "passive"))
      (node (ref "R31") (pin "1") (pinfunction "1_1") (pintype "passive"))
      (node (ref "R40") (pin "1") (pinfunction "1_1") (pintype "passive"))
      (node (ref "R42") (pin "1") (pinfunction "1_1") (pintype "passive"))
      (node (ref "R48") (pin "1") (pinfunction "1_1") (pintype "passive"))
      (node (ref "R5") (pin "1") (pinfunction "1_1") (pintype "passive"))
      (node (ref "R62") (pin "1") (pinfunction "1_1") (pintype "passive"))
      (node (ref "R7") (pin "1") (pinfunction "1_1") (pintype "passive"))
      (node (ref "U2") (pin "4") (pinfunction "COM_4") (pintype "passive"))
      (node (ref "U3") (pin "3") (pinfunction "GND_3") (pintype "passive"))
      (node (ref "U3") (pin "5") (pinfunction "~{EN}_5") (pintype "passive"))
      (node (ref "U4") (pin "4") (pinfunction "COM_4") (pintype "passive"))
      (node (ref "U5") (pin "4") (pinfunction "COM_4") (pintype "passive"))
      (node (ref "U6") (pin "2") (pinfunction "GND_2") (pintype "passive"))
    )
    (net (code "167") (name "Net-(D1-2)") (class "Default")
      (node (ref "C7") (pin "1") (pintype "passive"))
      (node (ref "D1") (pin "K") (pinfunction "2_K") (pintype "passive"))
      (node (ref "U2") (pin "8") (pinfunction "VB_8") (pintype "passive"))
    )
    (net (code "168") (name "Net-(D3-2)") (class "Default")
      (node (ref "C15") (pin "1") (pintype "passive"))
      (node (ref "D3") (pin "K") (pinfunction "2_K") (pintype "passive"))
      (node (ref "U4") (pin "8") (pinfunction "VB_8") (pintype "passive"))
    )
    (net (code "169") (name "Net-(D4-2)") (class "Default")
      (node (ref "C22") (pin "1") (pintype "passive"))
      (node (ref "D4") (pin "K") (pinfunction "2_K") (pintype "passive"))
      (node (ref "U5") (pin "8") (pinfunction "VB_8") (pintype "passive"))
    )
    (net (code "170") (name "Net-(D5-2)") (class "Default")
      (node (ref "D5") (pin "K") (pinfunction "2_K") (pintype "passive"))
      (node (ref "L1") (pin "1") (pinfunction "1_1") (pintype "passive"))
      (node (ref "U3") (pin "2") (pinfunction "VOUT_2") (pintype "passive"))
    )
    (net (code "171") (name "Net-(F1-Pad1)") (class "Default")
      (node (ref "F1") (pin "1") (pinfunction "1_1") (pintype "passive"))
      (node (ref "J1") (pin "1") (pinfunction "1_1") (pintype "passive"))
    )
    (net (code "172") (name "Net-(J3-Pad1)") (class "Default")
      (node (ref "J3") (pin "1") (pinfunction "1_1") (pintype "passive"))
      (node (ref "R51") (pin "1") (pinfunction "1_1") (pintype "passive"))
    )
    (net (code "173") (name "Net-(J3-Pad2)") (class "Default")
      (node (ref "J3") (pin "2") (pinfunction "2_2") (pintype "passive"))
      (node (ref "R57") (pin "1") (pinfunction "1_1") (pintype "passive"))
    )
    (net (code "174") (name "Net-(J3-Pad3)") (class "Default")
      (node (ref "J3") (pin "3") (pinfunction "3_3") (pintype "passive"))
      (node (ref "R59") (pin "1") (pinfunction "1_1") (pintype "passive"))
    )
    (net (code "175") (name "Net-(LED-PadA)") (class "Default")
      (node (ref "LED") (pin "A") (pinfunction "A_A") (pintype "passive"))
      (node (ref "R66") (pin "1") (pinfunction "1_1") (pintype "passive"))
    )
    (net (code "176") (name "Net-(Q1-G)") (class "Default")
      (node (ref "Q1") (pin "1") (pinfunction "G_1") (pintype "input"))
      (node (ref "R1") (pin "2") (pinfunction "2_2") (pintype "passive"))
      (node (ref "R3") (pin "2") (pinfunction "2_2") (pintype "passive"))
    )
    (net (code "177") (name "Net-(Q2-G)") (class "Default")
      (node (ref "Q2") (pin "1") (pinfunction "G_1") (pintype "input"))
      (node (ref "R12") (pin "2") (pinfunction "2_2") (pintype "passive"))
      (node (ref "R8") (pin "2") (pinfunction "2_2") (pintype "passive"))
    )
    (net (code "178") (name "Net-(Q3-G)") (class "Default")
      (node (ref "Q3") (pin "1") (pinfunction "G_1") (pintype "input"))
      (node (ref "R17") (pin "2") (pinfunction "2_2") (pintype "passive"))
      (node (ref "R19") (pin "2") (pinfunction "2_2") (pintype "passive"))
    )
    (net (code "179") (name "Net-(Q4-G)") (class "Default")
      (node (ref "Q4") (pin "1") (pinfunction "G_1") (pintype "input"))
      (node (ref "R26") (pin "2") (pinfunction "2_2") (pintype "passive"))
      (node (ref "R30") (pin "2") (pinfunction "2_2") (pintype "passive"))
    )
    (net (code "180") (name "Net-(Q5-G)") (class "Default")
      (node (ref "Q5") (pin "1") (pinfunction "G_1") (pintype "input"))
      (node (ref "R32") (pin "2") (pinfunction "2_2") (pintype "passive"))
      (node (ref "R34") (pin "2") (pinfunction "2_2") (pintype "passive"))
    )
    (net (code "181") (name "Net-(Q6-G)") (class "Default")
      (node (ref "Q6") (pin "1") (pinfunction "G_1") (pintype "input"))
      (node (ref "R45") (pin "2") (pinfunction "2_2") (pintype "passive"))
      (node (ref "R49") (pin "2") (pinfunction "2_2") (pintype "passive"))
    )
    (net (code "182") (name "Net-(U1A-+)") (class "Default")
      (node (ref "C9") (pin "1") (pintype "passive"))
      (node (ref "R2") (pin "1") (pinfunction "1_1") (pintype "passive"))
      (node (ref "R4") (pin "2") (pinfunction "2_2") (pintype "passive"))
      (node (ref "U1") (pin "3") (pinfunction "+_3") (pintype "passive"))
    )
    (net (code "183") (name "Net-(U1A--)") (class "Default")
      (node (ref "C9") (pin "2") (pintype "passive"))
      (node (ref "R15") (pin "2") (pinfunction "2_2") (pintype "passive"))
      (node (ref "R5") (pin "2") (pinfunction "2_2") (pintype "passive"))
      (node (ref "U1") (pin "2") (pinfunction "-_2") (pintype "passive"))
    )
    (net (code "184") (name "Net-(U1A-O)") (class "Default")
      (node (ref "R13") (pin "1") (pinfunction "1_1") (pintype "passive"))
      (node (ref "R15") (pin "1") (pinfunction "1_1") (pintype "passive"))
      (node (ref "U1") (pin "1") (pinfunction "O_1") (pintype "passive"))
    )
    (net (code "185") (name "Net-(U1B-+)") (class "Default")
      (node (ref "C16") (pin "1") (pintype "passive"))
      (node (ref "R18") (pin "1") (pinfunction "1_1") (pintype "passive"))
      (node (ref "R20") (pin "2") (pinfunction "2_2") (pintype "passive"))
      (node (ref "U1") (pin "5") (pinfunction "+_5") (pintype "passive"))
    )
    (net (code "186") (name "Net-(U1B--)") (class "Default")
      (node (ref "C16") (pin "2") (pintype "passive"))
      (node (ref "R24") (pin "2") (pinfunction "2_2") (pintype "passive"))
      (node (ref "R28") (pin "2") (pinfunction "2_2") (pintype "passive"))
      (node (ref "U1") (pin "6") (pinfunction "-_6") (pintype "passive"))
    )
    (net (code "187") (name "Net-(U1B-O)") (class "Default")
      (node (ref "R21") (pin "1") (pinfunction "1_1") (pintype "passive"))
      (node (ref "R28") (pin "1") (pinfunction "1_1") (pintype "passive"))
      (node (ref "U1") (pin "7") (pinfunction "O_7") (pintype "passive"))
    )
    (net (code "188") (name "Net-(U1C-+)") (class "Default")
      (node (ref "C23") (pin "1") (pintype "passive"))
      (node (ref "R33") (pin "1") (pinfunction "1_1") (pintype "passive"))
      (node (ref "R35") (pin "2") (pinfunction "2_2") (pintype "passive"))
      (node (ref "U1") (pin "10") (pinfunction "+_10") (pintype "passive"))
    )
    (net (code "189") (name "Net-(U1C--)") (class "Default")
      (node (ref "C23") (pin "2") (pintype "passive"))
      (node (ref "R40") (pin "2") (pinfunction "2_2") (pintype "passive"))
      (node (ref "R46") (pin "2") (pinfunction "2_2") (pintype "passive"))
      (node (ref "U1") (pin "9") (pinfunction "-_9") (pintype "passive"))
    )
    (net (code "190") (name "Net-(U1C-O)") (class "Default")
      (node (ref "R37") (pin "1") (pinfunction "1_1") (pintype "passive"))
      (node (ref "R46") (pin "1") (pinfunction "1_1") (pintype "passive"))
      (node (ref "U1") (pin "8") (pinfunction "O_8") (pintype "passive"))
    )
    (net (code "191") (name "Net-(U1D--)") (class "Default")
      (node (ref "C27") (pin "1") (pintype "passive"))
      (node (ref "R44") (pin "2") (pinfunction "2_2") (pintype "passive"))
      (node (ref "U1") (pin "13") (pinfunction "-_13") (pintype "passive"))
    )
    (net (code "192") (name "Net-(U2-HO)") (class "Default")
      (node (ref "R1") (pin "1") (pinfunction "1_1") (pintype "passive"))
      (node (ref "U2") (pin "7") (pinfunction "HO_7") (pintype "passive"))
    )
    (net (code "193") (name "Net-(U2-LO)") (class "Default")
      (node (ref "R8") (pin "1") (pinfunction "1_1") (pintype "passive"))
      (node (ref "U2") (pin "5") (pinfunction "LO_5") (pintype "passive"))
    )
    (net (code "194") (name "Net-(U3-FEEDBACK)") (class "Default")
      (node (ref "C8") (pin "2") (pintype "passive"))
      (node (ref "R11") (pin "1") (pinfunction "1_1") (pintype "passive"))
      (node (ref "R16") (pin "2") (pinfunction "2_2") (pintype "passive"))
      (node (ref "U3") (pin "4") (pinfunction "FEEDBACK_4") (pintype "passive"))
    )
    (net (code "195") (name "Net-(U4-HO)") (class "Default")
      (node (ref "R17") (pin "1") (pinfunction "1_1") (pintype "passive"))
      (node (ref "U4") (pin "7") (pinfunction "HO_7") (pintype "passive"))
    )
    (net (code "196") (name "Net-(U4-LO)") (class "Default")
      (node (ref "R26") (pin "1") (pinfunction "1_1") (pintype "passive"))
      (node (ref "U4") (pin "5") (pinfunction "LO_5") (pintype "passive"))
    )
    (net (code "197") (name "Net-(U5-HO)") (class "Default")
      (node (ref "R32") (pin "1") (pinfunction "1_1") (pintype "passive"))
      (node (ref "U5") (pin "7") (pinfunction "HO_7") (pintype "passive"))
    )
    (net (code "198") (name "Net-(U5-LO)") (class "Default")
      (node (ref "R45") (pin "1") (pinfunction "1_1") (pintype "passive"))
      (node (ref "U5") (pin "5") (pinfunction "LO_5") (pintype "passive"))
    )
    (net (code "199") (name "VA3.3") (class "Default")
      (node (ref "C4") (pin "1") (pintype "passive"))
      (node (ref "L2") (pin "1") (pinfunction "1_1") (pintype "passive"))
      (node (ref "R18") (pin "2") (pinfunction "2_2") (pintype "passive"))
      (node (ref "R2") (pin "2") (pinfunction "2_2") (pintype "passive"))
      (node (ref "R33") (pin "2") (pinfunction "2_2") (pintype "passive"))
      (node (ref "U1") (pin "4") (pinfunction "V+_4") (pintype "passive"))
    )
    (net (code "200") (name "VIN+") (class "Default")
      (node (ref "C1") (pin "1") (pintype "passive"))
      (node (ref "C2") (pin "1") (pintype "passive"))
      (node (ref "CE1") (pin "1") (pinfunction "1_1") (pintype "passive"))
      (node (ref "CE2") (pin "1") (pinfunction "1_1") (pintype "passive"))
      (node (ref "CE3") (pin "1") (pinfunction "1_1") (pintype "passive"))
      (node (ref "D2") (pin "K") (pinfunction "2_K") (pintype "passive"))
      (node (ref "F1") (pin "2") (pinfunction "2_2") (pintype "passive"))
      (node (ref "Q1") (pin "2") (pinfunction "D_2") (pintype "input"))
      (node (ref "Q3") (pin "2") (pinfunction "D_2") (pintype "input"))
      (node (ref "Q5") (pin "2") (pinfunction "D_2") (pintype "input"))
      (node (ref "R25") (pin "2") (pinfunction "2_2") (pintype "passive"))
      (node (ref "U3") (pin "1") (pinfunction "VIN_1") (pintype "passive"))
    )
  )
)
